# Power_12V-0_5A.net
KiCad netlist of a schematic drawn in EAGLE
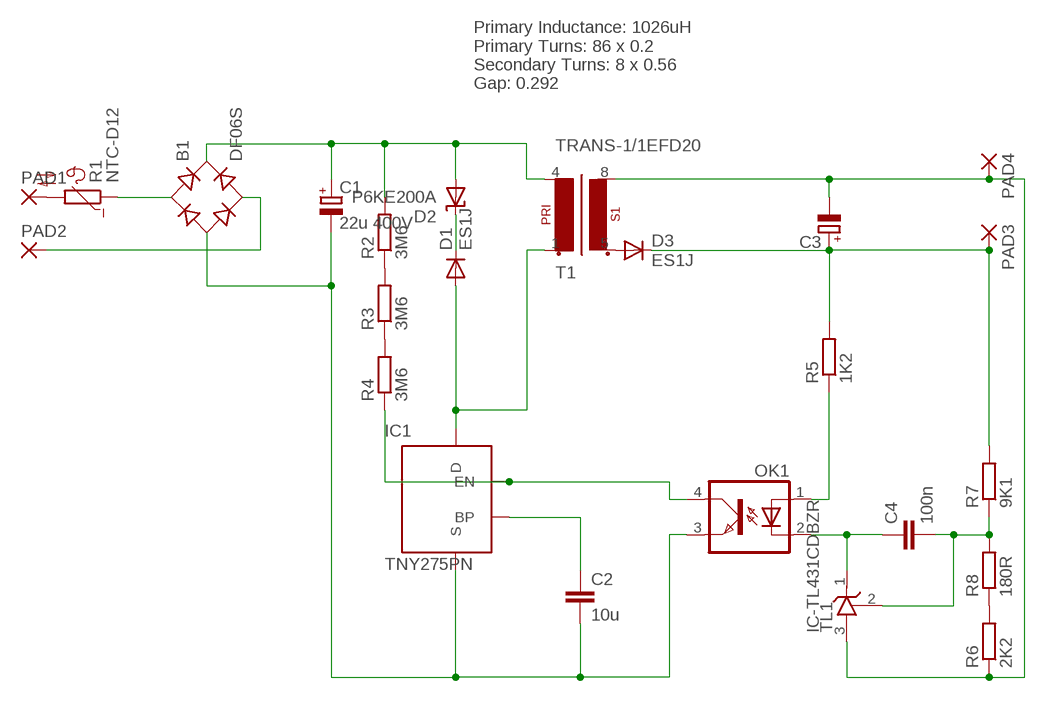
[diagram p0: schematic, sheet 1]

(export (version "E")
  (design (tool "Eeschema 10.0.6"))
  (components
    (comp (ref "B1")
      (value "DF06S")
      (footprint "eagle-import:DFS")
      (libsource (lib "eagle-import") (part "DFS06"))
    )
    (comp (ref "C1")
      (value "22u 400V")
      (footprint "eagle-import:E5-13")
      (libsource (lib "eagle-import") (part "CPOL-EUE5-13"))
    )
    (comp (ref "C2")
      (value "10u")
      (footprint "eagle-import:C1210")
      (libsource (lib "eagle-import") (part "CAP_1210"))
    )
    (comp (ref "C3")
      (value "CPOL-EUE7.5-18")
      (footprint "eagle-import:E7,5-18")
      (libsource (lib "eagle-import") (part "CPOL-EUE7.5-18"))
    )
    (comp (ref "C4")
      (value "100n")
      (footprint "eagle-import:C0805")
      (libsource (lib "eagle-import") (part "CAP_0805"))
    )
    (comp (ref "D1")
      (value "ES1J")
      (footprint "eagle-import:DO214AC")
      (libsource (lib "eagle-import") (part "DIODE_ES1J"))
    )
    (comp (ref "D2")
      (value "P6KE200A")
      (footprint "eagle-import:DO15-12")
      (libsource (lib "eagle-import") (part "SUPRESSORDO-204AC"))
    )
    (comp (ref "D3")
      (value "ES1J")
      (footprint "eagle-import:DO214AC")
      (libsource (lib "eagle-import") (part "DIODE_ES1J"))
    )
    (comp (ref "IC1")
      (value "TNY275PN")
      (footprint "eagle-import:DIP-8C")
      (libsource (lib "eagle-import") (part "POWER-TNY275"))
    )
    (comp (ref "OK1")
      (value "OPTOTRANSPC817")
      (footprint "eagle-import:DIL04")
      (fields (field (name "MPN") "PC817X4J000F"))
      (libsource (lib "eagle-import") (part "OPTOTRANSPC817"))
    )
    (comp (ref "PAD1")
      (value "SMD5")
      (footprint "eagle-import:SMD2,54-5,08")
      (libsource (lib "eagle-import") (part "SMD5"))
    )
    (comp (ref "PAD2")
      (value "SMD5")
      (footprint "eagle-import:SMD2,54-5,08")
      (libsource (lib "eagle-import") (part "SMD5"))
    )
    (comp (ref "PAD3")
      (value "SMD5")
      (footprint "eagle-import:SMD2,54-5,08")
      (libsource (lib "eagle-import") (part "SMD5"))
    )
    (comp (ref "PAD4")
      (value "SMD5")
      (footprint "eagle-import:SMD2,54-5,08")
      (libsource (lib "eagle-import") (part "SMD5"))
    )
    (comp (ref "R1")
      (value "NTC-D12")
      (footprint "eagle-import:NTC-D12")
      (libsource (lib "eagle-import") (part "NTC-D12"))
    )
    (comp (ref "R2")
      (value "3M6")
      (footprint "eagle-import:R0805")
      (libsource (lib "eagle-import") (part "R_0805"))
    )
    (comp (ref "R3")
      (value "3M6")
      (footprint "eagle-import:R0805")
      (libsource (lib "eagle-import") (part "R_0805"))
    )
    (comp (ref "R4")
      (value "3M6")
      (footprint "eagle-import:R0805")
      (libsource (lib "eagle-import") (part "R_0805"))
    )
    (comp (ref "R5")
      (value "1K2")
      (footprint "eagle-import:R1206")
      (libsource (lib "eagle-import") (part "R_1206"))
    )
    (comp (ref "R6")
      (value "2K2")
      (footprint "eagle-import:RESC2012X50")
      (libsource (lib "eagle-import") (part "R_R0805"))
    )
    (comp (ref "R7")
      (value "9K1")
      (footprint "eagle-import:R1206")
      (libsource (lib "eagle-import") (part "R_1206"))
    )
    (comp (ref "R8")
      (value "180R")
      (footprint "eagle-import:R1206")
      (libsource (lib "eagle-import") (part "R_1206"))
    )
    (comp (ref "T1")
      (value "TRANS-1/1EFD20")
      (footprint "eagle-import:EFD20_8PIN")
      (libsource (lib "eagle-import") (part "TRANS-1/1EFD20"))
    )
    (comp (ref "TL1")
      (value "IC-TL431CDBZR")
      (footprint "eagle-import:SOT23")
      (libsource (lib "eagle-import") (part "IC-TL431CDBZR"))
    )
  )
  (nets
    (net (code "1") (name "Net-(B1-PadAC1)") (class "Default")
      (node (ref "B1") (pin "AC1") (pinfunction "AC1_AC1") (pintype "passive"))
      (node (ref "R1") (pin "1") (pinfunction "1_1") (pintype "passive"))
    )
    (net (code "2") (name "Net-(D1-PadC)") (class "Default")
      (node (ref "D1") (pin "C") (pinfunction "C_C") (pintype "passive"))
      (node (ref "D2") (pin "C") (pinfunction "C_C") (pintype "passive"))
    )
    (net (code "3") (name "Net-(IC1-BP)") (class "Default")
      (node (ref "C2") (pin "1") (pinfunction "1_1") (pintype "passive"))
      (node (ref "IC1") (pin "2") (pinfunction "BP_2") (pintype "input"))
    )
    (net (code "4") (name "Net-(IC1-D)") (class "Default")
      (node (ref "D1") (pin "A") (pinfunction "A_A") (pintype "passive"))
      (node (ref "IC1") (pin "4") (pinfunction "D_4") (pintype "input"))
      (node (ref "T1") (pin "1") (pinfunction "P1-1_1") (pintype "passive"))
    )
    (net (code "5") (name "Net-(IC1-EN)") (class "Default")
      (node (ref "IC1") (pin "1") (pinfunction "EN_1") (pintype "input"))
      (node (ref "OK1") (pin "4") (pinfunction "COL_4") (pintype "passive"))
      (node (ref "R4") (pin "1") (pinfunction "1_1") (pintype "passive"))
    )
    (net (code "6") (name "Net-(OK1-A)") (class "Default")
      (node (ref "OK1") (pin "1") (pinfunction "A_1") (pintype "passive"))
      (node (ref "R5") (pin "1") (pinfunction "1_1") (pintype "passive"))
    )
    (net (code "7") (name "Net-(OK1-C)") (class "Default")
      (node (ref "C4") (pin "1") (pinfunction "1_1") (pintype "passive"))
      (node (ref "OK1") (pin "2") (pinfunction "C_2") (pintype "passive"))
      (node (ref "TL1") (pin "1") (pinfunction "C_1") (pintype "passive"))
    )
    (net (code "8") (name "Net-(OK1-EMIT)") (class "Default")
      (node (ref "B1") (pin "-") (pinfunction "-_-") (pintype "passive"))
      (node (ref "C1") (pin "-") (pinfunction "-_-") (pintype "passive"))
      (node (ref "C2") (pin "2") (pinfunction "2_2") (pintype "passive"))
      (node (ref "IC1") (pin "5") (pinfunction "S_5") (pintype "input"))
      (node (ref "IC1") (pin "6") (pinfunction "S_6") (pintype "input"))
      (node (ref "IC1") (pin "7") (pinfunction "S_7") (pintype "input"))
      (node (ref "IC1") (pin "8") (pinfunction "S_8") (pintype "input"))
      (node (ref "OK1") (pin "3") (pinfunction "EMIT_3") (pintype "passive"))
    )
    (net (code "9") (name "Net-(PAD1-P)") (class "Default")
      (node (ref "PAD1") (pin "1") (pinfunction "P_1") (pintype "passive"))
      (node (ref "R1") (pin "2") (pinfunction "2_2") (pintype "passive"))
    )
    (net (code "10") (name "Net-(PAD2-P)") (class "Default")
      (node (ref "B1") (pin "AC2") (pinfunction "AC2_AC2") (pintype "passive"))
      (node (ref "PAD2") (pin "1") (pinfunction "P_1") (pintype "passive"))
    )
    (net (code "11") (name "Net-(PAD3-P)") (class "Default")
      (node (ref "C3") (pin "+") (pinfunction "+_+") (pintype "passive"))
      (node (ref "D3") (pin "C") (pinfunction "C_C") (pintype "passive"))
      (node (ref "PAD3") (pin "1") (pinfunction "P_1") (pintype "passive"))
      (node (ref "R5") (pin "2") (pinfunction "2_2") (pintype "passive"))
      (node (ref "R7") (pin "2") (pinfunction "2_2") (pintype "passive"))
    )
    (net (code "12") (name "Net-(PAD4-P)") (class "Default")
      (node (ref "C3") (pin "-") (pinfunction "-_-") (pintype "passive"))
      (node (ref "PAD4") (pin "1") (pinfunction "P_1") (pintype "passive"))
      (node (ref "R6") (pin "1") (pinfunction "1_1") (pintype "passive"))
      (node (ref "T1") (pin "8") (pinfunction "S1-2_8") (pintype "passive"))
      (node (ref "TL1") (pin "3") (pinfunction "A_3") (pintype "passive"))
    )
    (net (code "13") (name "Net-(R2-Pad1)") (class "Default")
      (node (ref "R2") (pin "1") (pinfunction "1_1") (pintype "passive"))
      (node (ref "R3") (pin "2") (pinfunction "2_2") (pintype "passive"))
    )
    (net (code "14") (name "Net-(R3-Pad1)") (class "Default")
      (node (ref "R3") (pin "1") (pinfunction "1_1") (pintype "passive"))
      (node (ref "R4") (pin "2") (pinfunction "2_2") (pintype "passive"))
    )
    (net (code "15") (name "Net-(R6-Pad2)") (class "Default")
      (node (ref "R6") (pin "2") (pinfunction "2_2") (pintype "passive"))
      (node (ref "R8") (pin "1") (pinfunction "1_1") (pintype "passive"))
    )
    (net (code "16") (name "Net-(T1-P1-2)") (class "Default")
      (node (ref "B1") (pin "+") (pinfunction "+_+") (pintype "passive"))
      (node (ref "C1") (pin "+") (pinfunction "+_+") (pintype "passive"))
      (node (ref "D2") (pin "A") (pinfunction "A_A") (pintype "passive"))
      (node (ref "R2") (pin "2") (pinfunction "2_2") (pintype "passive"))
      (node (ref "T1") (pin "4") (pinfunction "P1-2_4") (pintype "passive"))
    )
    (net (code "17") (name "Net-(T1-S1-1)") (class "Default")
      (node (ref "D3") (pin "A") (pinfunction "A_A") (pintype "passive"))
      (node (ref "T1") (pin "5") (pinfunction "S1-1_5") (pintype "passive"))
    )
    (net (code "18") (name "Net-(TL1-R)") (class "Default")
      (node (ref "C4") (pin "2") (pinfunction "2_2") (pintype "passive"))
      (node (ref "R7") (pin "1") (pinfunction "1_1") (pintype "passive"))
      (node (ref "R8") (pin "2") (pinfunction "2_2") (pintype "passive"))
      (node (ref "TL1") (pin "2") (pinfunction "R_2") (pintype "passive"))
    )
  )
)
